# STM32F100_Base_Wireless.net
KiCad netlist of a schematic drawn in EAGLE
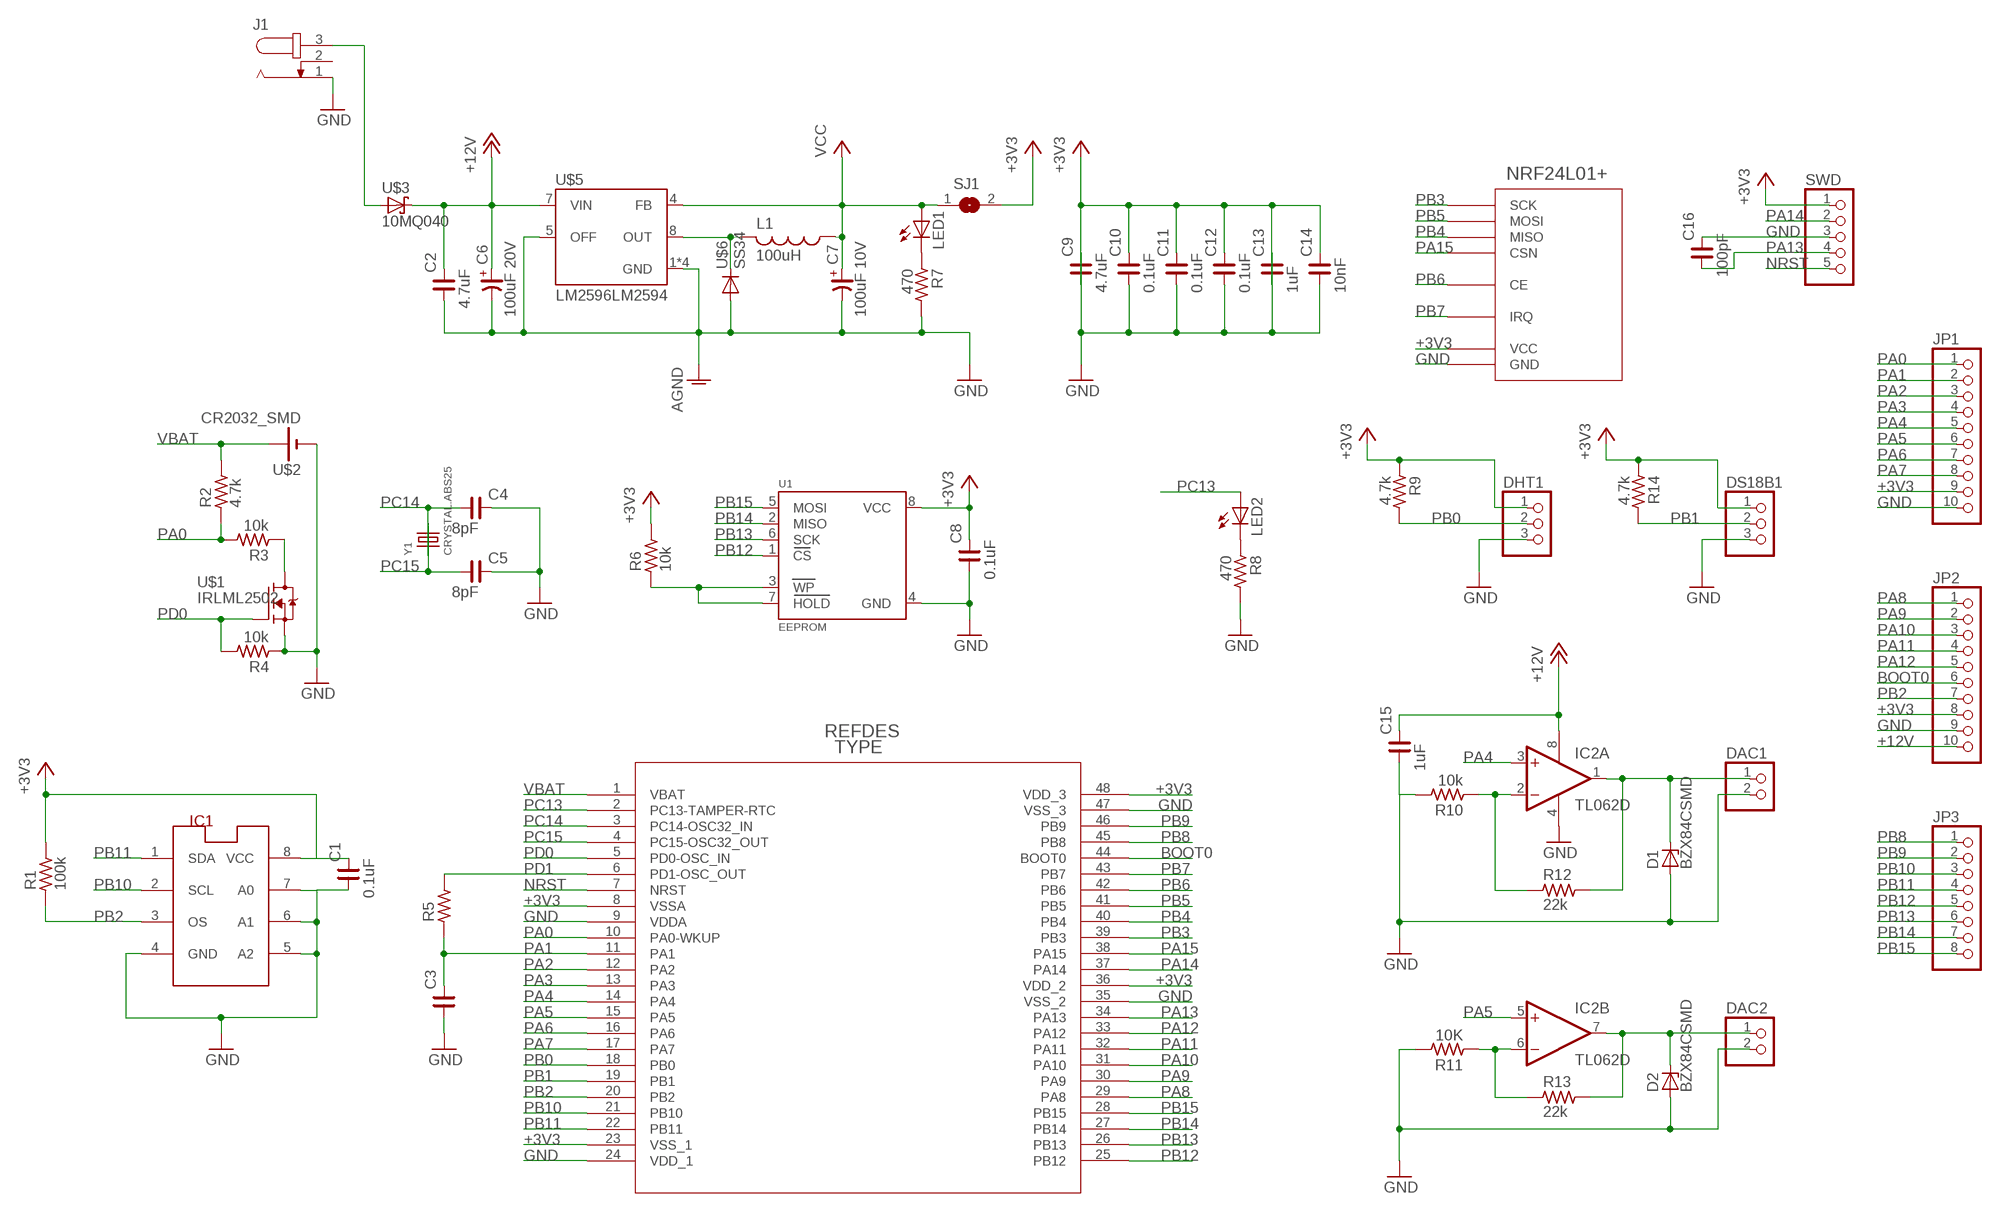
[diagram p0: schematic, sheet 1]

(export (version "E")
  (design (tool "Eeschema 10.0.6"))
  (components
    (comp (ref "C1")
      (value "0.1uF")
      (footprint "eagle-import:C1206")
      (libsource (lib "eagle-import") (part "C_1206"))
    )
    (comp (ref "C2")
      (value "4.7uF")
      (footprint "eagle-import:C1206")
      (libsource (lib "eagle-import") (part "C_1206"))
    )
    (comp (ref "C3")
      (value "C_1206")
      (footprint "eagle-import:C1206")
      (libsource (lib "eagle-import") (part "C_1206"))
    )
    (comp (ref "C4")
      (value "8pF")
      (footprint "eagle-import:C0603")
      (libsource (lib "eagle-import") (part "C_0603"))
    )
    (comp (ref "C5")
      (value "8pF")
      (footprint "eagle-import:C0603")
      (libsource (lib "eagle-import") (part "C_0603"))
    )
    (comp (ref "C6")
      (value "100uF 20V")
      (footprint "eagle-import:C7343_T")
      (libsource (lib "eagle-import") (part "CP_7343"))
    )
    (comp (ref "C7")
      (value "100uF 10V")
      (footprint "eagle-import:C6032-28_T")
      (libsource (lib "eagle-import") (part "CP_6032-28"))
    )
    (comp (ref "C8")
      (value "0.1uF")
      (footprint "eagle-import:C1206")
      (libsource (lib "eagle-import") (part "C_1206"))
    )
    (comp (ref "C9")
      (value "4.7uF")
      (footprint "eagle-import:C1206")
      (libsource (lib "eagle-import") (part "C_1206"))
    )
    (comp (ref "C10")
      (value "0.1uF")
      (footprint "eagle-import:C0603")
      (libsource (lib "eagle-import") (part "C_0603"))
    )
    (comp (ref "C11")
      (value "0.1uF")
      (footprint "eagle-import:C0603")
      (libsource (lib "eagle-import") (part "C_0603"))
    )
    (comp (ref "C12")
      (value "0.1uF")
      (footprint "eagle-import:C0603")
      (libsource (lib "eagle-import") (part "C_0603"))
    )
    (comp (ref "C13")
      (value "1uF")
      (footprint "eagle-import:C1206")
      (libsource (lib "eagle-import") (part "C_1206"))
    )
    (comp (ref "C14")
      (value "10nF")
      (footprint "eagle-import:C0603")
      (libsource (lib "eagle-import") (part "C_0603"))
    )
    (comp (ref "C15")
      (value "1uF")
      (footprint "eagle-import:C1206")
      (libsource (lib "eagle-import") (part "C_1206"))
    )
    (comp (ref "C16")
      (value "100pF")
      (footprint "eagle-import:C1206")
      (libsource (lib "eagle-import") (part "C_1206"))
    )
    (comp (ref "D1")
      (value "BZX84CSMD")
      (footprint "eagle-import:TO236")
      (libsource (lib "eagle-import") (part "BZX84CSMD"))
    )
    (comp (ref "D2")
      (value "BZX84CSMD")
      (footprint "eagle-import:TO236")
      (libsource (lib "eagle-import") (part "BZX84CSMD"))
    )
    (comp (ref "DAC1")
      (value "PINHD-1X02_2.54-S")
      (footprint "eagle-import:1X02-S")
      (libsource (lib "eagle-import") (part "PINHD-1X02_2.54-S"))
    )
    (comp (ref "DAC2")
      (value "PINHD-1X02_2.54-S")
      (footprint "eagle-import:1X02-S")
      (libsource (lib "eagle-import") (part "PINHD-1X02_2.54-S"))
    )
    (comp (ref "DHT1")
      (value "PINHD-1X03_2.54-S")
      (footprint "eagle-import:1X03-S")
      (libsource (lib "eagle-import") (part "PINHD-1X03_2.54-S"))
    )
    (comp (ref "DS18B1")
      (value "PINHD-1X03_2.54-S")
      (footprint "eagle-import:1X03-S")
      (libsource (lib "eagle-import") (part "PINHD-1X03_2.54-S"))
    )
    (comp (ref "IC1")
      (value "LM75_ICN")
      (footprint "eagle-import:SO8_LM75")
      (libsource (lib "eagle-import") (part "LM75_ICN"))
    )
    (comp (ref "IC2")
      (value "TL062D")
      (footprint "eagle-import:SO08")
      (libsource (lib "eagle-import") (part "TL062D"))
    )
    (comp (ref "J1")
      (value "JACK-PLUG0")
      (footprint "eagle-import:SPC4077")
      (libsource (lib "eagle-import") (part "JACK-PLUG0"))
    )
    (comp (ref "JP1")
      (value "PINHD-1X10_2.54-S")
      (footprint "eagle-import:1X10-S")
      (libsource (lib "eagle-import") (part "PINHD-1X10_2.54-S"))
    )
    (comp (ref "JP2")
      (value "PINHD-1X10_2.54-S")
      (footprint "eagle-import:1X10-S")
      (libsource (lib "eagle-import") (part "PINHD-1X10_2.54-S"))
    )
    (comp (ref "JP3")
      (value "PINHD-1X08_2.54-S")
      (footprint "eagle-import:1X08-S")
      (libsource (lib "eagle-import") (part "PINHD-1X08_2.54-S"))
    )
    (comp (ref "L1")
      (value "100uH")
      (footprint "eagle-import:POWER-CHOKE_WE-TPC")
      (libsource (lib "eagle-import") (part "L-USWE-TPC"))
    )
    (comp (ref "LED1")
      (value "LEDCHIPLED_1206")
      (footprint "eagle-import:CHIPLED_1206")
      (libsource (lib "eagle-import") (part "LEDCHIPLED_1206"))
    )
    (comp (ref "LED2")
      (value "LEDCHIPLED_1206")
      (footprint "eagle-import:CHIPLED_1206")
      (libsource (lib "eagle-import") (part "LEDCHIPLED_1206"))
    )
    (comp (ref "R1")
      (value "100k")
      (footprint "eagle-import:R1206")
      (libsource (lib "eagle-import") (part "R_1206"))
    )
    (comp (ref "R2")
      (value "4.7k")
      (footprint "eagle-import:R1206")
      (libsource (lib "eagle-import") (part "R_1206"))
    )
    (comp (ref "R3")
      (value "10k")
      (footprint "eagle-import:R1206")
      (libsource (lib "eagle-import") (part "R_1206"))
    )
    (comp (ref "R4")
      (value "10k")
      (footprint "eagle-import:R1206")
      (libsource (lib "eagle-import") (part "R_1206"))
    )
    (comp (ref "R5")
      (value "R_1206")
      (footprint "eagle-import:R1206")
      (libsource (lib "eagle-import") (part "R_1206"))
    )
    (comp (ref "R6")
      (value "10k")
      (footprint "eagle-import:R1206")
      (libsource (lib "eagle-import") (part "R_1206"))
    )
    (comp (ref "R7")
      (value "470")
      (footprint "eagle-import:R1206")
      (libsource (lib "eagle-import") (part "R_1206"))
    )
    (comp (ref "R8")
      (value "470")
      (footprint "eagle-import:R1206")
      (libsource (lib "eagle-import") (part "R_1206"))
    )
    (comp (ref "R9")
      (value "4.7k")
      (footprint "eagle-import:R1206")
      (libsource (lib "eagle-import") (part "R_1206"))
    )
    (comp (ref "R10")
      (value "10k")
      (footprint "eagle-import:R1206")
      (libsource (lib "eagle-import") (part "R_1206"))
    )
    (comp (ref "R11")
      (value "10K")
      (footprint "eagle-import:R1206")
      (libsource (lib "eagle-import") (part "R_1206"))
    )
    (comp (ref "R12")
      (value "22k")
      (footprint "eagle-import:R1206")
      (libsource (lib "eagle-import") (part "R_1206"))
    )
    (comp (ref "R13")
      (value "22k")
      (footprint "eagle-import:R1206")
      (libsource (lib "eagle-import") (part "R_1206"))
    )
    (comp (ref "R14")
      (value "4.7k")
      (footprint "eagle-import:R1206")
      (libsource (lib "eagle-import") (part "R_1206"))
    )
    (comp (ref "SJ1") (value "SJ") (footprint "eagle-import:SJ") (libsource (lib "eagle-import") (part "SJ")))
    (comp (ref "SWD")
      (value "PINHD-1X05_2.54-90°-S")
      (footprint "eagle-import:1X05_90-S")
      (libsource (lib "eagle-import") (part "PINHD-1X05_2.54-90°-S"))
    )
    (comp (ref "U$1")
      (value "IRLML2502")
      (footprint "eagle-import:SOT23")
      (libsource (lib "eagle-import") (part "IRLML2502"))
    )
    (comp (ref "U$2")
      (value "CR2032_SMD")
      (footprint "eagle-import:SMD_BH-2")
      (libsource (lib "eagle-import") (part "CR2032_SMD"))
    )
    (comp (ref "U$3")
      (value "10MQ040")
      (footprint "eagle-import:SMA")
      (libsource (lib "eagle-import") (part "10MQ040"))
    )
    (comp (ref "U$4")
      (value "STM32F100C8T6B")
      (footprint "eagle-import:LQFP-48")
      (libsource (lib "eagle-import") (part "STM32F100C8T6B"))
    )
    (comp (ref "U$5")
      (value "LM2596LM2594")
      (footprint "eagle-import:SOIC8_150MIL")
      (libsource (lib "eagle-import") (part "LM2596LM2594"))
    )
    (comp (ref "U$6")
      (value "SS34")
      (footprint "eagle-import:DO214AC")
      (libsource (lib "eagle-import") (part "DIODE-DO214AC"))
    )
    (comp (ref "U$7")
      (value "NRF24L01+")
      (footprint "eagle-import:NRF24L01+")
      (libsource (lib "eagle-import") (part "NRF24L01+"))
    )
    (comp (ref "U1")
      (value "EEPROM")
      (footprint "eagle-import:SOIC8_150MIL")
      (libsource (lib "eagle-import") (part "EEPROM_SPI_AT25040A"))
    )
    (comp (ref "Y1")
      (value "CRYSTAL.ABS25")
      (footprint "eagle-import:ABS25")
      (libsource (lib "eagle-import") (part "CRYSTAL.ABS25"))
    )
  )
  (nets
    (net (code "1") (name "+3V3") (class "Default")
      (node (ref "C1") (pin "2") (pinfunction "2_2") (pintype "passive"))
      (node (ref "C10") (pin "2") (pinfunction "2_2") (pintype "passive"))
      (node (ref "C11") (pin "2") (pinfunction "2_2") (pintype "passive"))
      (node (ref "C12") (pin "2") (pinfunction "2_2") (pintype "passive"))
      (node (ref "C13") (pin "1") (pinfunction "1_1") (pintype "passive"))
      (node (ref "C14") (pin "2") (pinfunction "2_2") (pintype "passive"))
      (node (ref "C8") (pin "2") (pinfunction "2_2") (pintype "passive"))
      (node (ref "C9") (pin "1") (pinfunction "1_1") (pintype "passive"))
      (node (ref "DHT1") (pin "1") (pinfunction "1_1") (pintype "passive"))
      (node (ref "DS18B1") (pin "1") (pinfunction "1_1") (pintype "passive"))
      (node (ref "IC1") (pin "8") (pinfunction "VCC_8") (pintype "power_in"))
      (node (ref "JP1") (pin "9") (pinfunction "9_9") (pintype "passive"))
      (node (ref "JP2") (pin "8") (pinfunction "8_8") (pintype "passive"))
      (node (ref "R1") (pin "2") (pinfunction "2_2") (pintype "passive"))
      (node (ref "R14") (pin "1") (pinfunction "1_1") (pintype "passive"))
      (node (ref "R6") (pin "2") (pinfunction "2_2") (pintype "passive"))
      (node (ref "R9") (pin "1") (pinfunction "1_1") (pintype "passive"))
      (node (ref "SJ1") (pin "2") (pinfunction "2_2") (pintype "passive"))
      (node (ref "SWD") (pin "1") (pinfunction "1_1") (pintype "passive"))
      (node (ref "U$4") (pin "23") (pinfunction "VSS_1_23") (pintype "passive"))
      (node (ref "U$4") (pin "36") (pinfunction "VDD_2_36") (pintype "passive"))
      (node (ref "U$4") (pin "48") (pinfunction "VDD_3_48") (pintype "passive"))
      (node (ref "U$4") (pin "8") (pinfunction "VSSA_8") (pintype "passive"))
      (node (ref "U$7") (pin "VCC") (pinfunction "VCC_VCC") (pintype "passive"))
      (node (ref "U1") (pin "8") (pinfunction "VCC_8") (pintype "power_in"))
    )
    (net (code "2") (name "+12V") (class "Default")
      (node (ref "C15") (pin "2") (pinfunction "2_2") (pintype "passive"))
      (node (ref "C2") (pin "2") (pinfunction "2_2") (pintype "passive"))
      (node (ref "C6") (pin "+") (pinfunction "+_+") (pintype "passive"))
      (node (ref "IC2") (pin "8") (pinfunction "V+_8") (pintype "power_in"))
      (node (ref "JP2") (pin "10") (pinfunction "10_10") (pintype "passive"))
      (node (ref "U$3") (pin "C") (pinfunction "C_C") (pintype "passive"))
      (node (ref "U$5") (pin "7") (pinfunction "VIN_7") (pintype "power_in"))
    )
    (net (code "3") (name "/BOOT0") (class "Default")
      (node (ref "JP2") (pin "6") (pinfunction "6_6") (pintype "passive"))
      (node (ref "U$4") (pin "44") (pinfunction "BOOT0_44") (pintype "passive"))
    )
    (net (code "4") (name "/NRST") (class "Default")
      (node (ref "SWD") (pin "5") (pinfunction "5_5") (pintype "passive"))
      (node (ref "U$4") (pin "7") (pinfunction "NRST_7") (pintype "passive"))
    )
    (net (code "5") (name "/PA0") (class "Default")
      (node (ref "JP1") (pin "1") (pinfunction "1_1") (pintype "passive"))
      (node (ref "R2") (pin "1") (pinfunction "1_1") (pintype "passive"))
      (node (ref "R3") (pin "2") (pinfunction "2_2") (pintype "passive"))
      (node (ref "U$4") (pin "10") (pinfunction "PA0-WKUP_10") (pintype "passive"))
    )
    (net (code "6") (name "/PA1") (class "Default")
      (node (ref "C3") (pin "2") (pinfunction "2_2") (pintype "passive"))
      (node (ref "JP1") (pin "2") (pinfunction "2_2") (pintype "passive"))
      (node (ref "R5") (pin "1") (pinfunction "1_1") (pintype "passive"))
      (node (ref "U$4") (pin "11") (pinfunction "PA1_11") (pintype "passive"))
    )
    (net (code "7") (name "/PA2") (class "Default")
      (node (ref "JP1") (pin "3") (pinfunction "3_3") (pintype "passive"))
      (node (ref "U$4") (pin "12") (pinfunction "PA2_12") (pintype "passive"))
    )
    (net (code "8") (name "/PA3") (class "Default")
      (node (ref "JP1") (pin "4") (pinfunction "4_4") (pintype "passive"))
      (node (ref "U$4") (pin "13") (pinfunction "PA3_13") (pintype "passive"))
    )
    (net (code "9") (name "/PA4") (class "Default")
      (node (ref "IC2") (pin "3") (pinfunction "+IN_3") (pintype "input"))
      (node (ref "JP1") (pin "5") (pinfunction "5_5") (pintype "passive"))
      (node (ref "U$4") (pin "14") (pinfunction "PA4_14") (pintype "passive"))
    )
    (net (code "10") (name "/PA5") (class "Default")
      (node (ref "IC2") (pin "5") (pinfunction "+IN_5") (pintype "input"))
      (node (ref "JP1") (pin "6") (pinfunction "6_6") (pintype "passive"))
      (node (ref "U$4") (pin "15") (pinfunction "PA5_15") (pintype "passive"))
    )
    (net (code "11") (name "/PA6") (class "Default")
      (node (ref "JP1") (pin "7") (pinfunction "7_7") (pintype "passive"))
      (node (ref "U$4") (pin "16") (pinfunction "PA6_16") (pintype "passive"))
    )
    (net (code "12") (name "/PA7") (class "Default")
      (node (ref "JP1") (pin "8") (pinfunction "8_8") (pintype "passive"))
      (node (ref "U$4") (pin "17") (pinfunction "PA7_17") (pintype "passive"))
    )
    (net (code "13") (name "/PA8") (class "Default")
      (node (ref "JP2") (pin "1") (pinfunction "1_1") (pintype "passive"))
      (node (ref "U$4") (pin "29") (pinfunction "PA8_29") (pintype "passive"))
    )
    (net (code "14") (name "/PA9") (class "Default")
      (node (ref "JP2") (pin "2") (pinfunction "2_2") (pintype "passive"))
      (node (ref "U$4") (pin "30") (pinfunction "PA9_30") (pintype "passive"))
    )
    (net (code "15") (name "/PA10") (class "Default")
      (node (ref "JP2") (pin "3") (pinfunction "3_3") (pintype "passive"))
      (node (ref "U$4") (pin "31") (pinfunction "PA10_31") (pintype "passive"))
    )
    (net (code "16") (name "/PA11") (class "Default")
      (node (ref "JP2") (pin "4") (pinfunction "4_4") (pintype "passive"))
      (node (ref "U$4") (pin "32") (pinfunction "PA11_32") (pintype "passive"))
    )
    (net (code "17") (name "/PA12") (class "Default")
      (node (ref "JP2") (pin "5") (pinfunction "5_5") (pintype "passive"))
      (node (ref "U$4") (pin "33") (pinfunction "PA12_33") (pintype "passive"))
    )
    (net (code "18") (name "/PA13") (class "Default")
      (node (ref "C16") (pin "1") (pinfunction "1_1") (pintype "passive"))
      (node (ref "SWD") (pin "4") (pinfunction "4_4") (pintype "passive"))
      (node (ref "U$4") (pin "34") (pinfunction "PA13_34") (pintype "passive"))
    )
    (net (code "19") (name "/PA14") (class "Default")
      (node (ref "SWD") (pin "2") (pinfunction "2_2") (pintype "passive"))
      (node (ref "U$4") (pin "37") (pinfunction "PA14_37") (pintype "passive"))
    )
    (net (code "20") (name "/PA15") (class "Default")
      (node (ref "U$4") (pin "38") (pinfunction "PA15_38") (pintype "passive"))
      (node (ref "U$7") (pin "CSN") (pinfunction "CSN_CSN") (pintype "passive"))
    )
    (net (code "21") (name "/PB0") (class "Default")
      (node (ref "DHT1") (pin "2") (pinfunction "2_2") (pintype "passive"))
      (node (ref "R9") (pin "2") (pinfunction "2_2") (pintype "passive"))
      (node (ref "U$4") (pin "18") (pinfunction "PB0_18") (pintype "passive"))
    )
    (net (code "22") (name "/PB1") (class "Default")
      (node (ref "DS18B1") (pin "2") (pinfunction "2_2") (pintype "passive"))
      (node (ref "R14") (pin "2") (pinfunction "2_2") (pintype "passive"))
      (node (ref "U$4") (pin "19") (pinfunction "PB1_19") (pintype "passive"))
    )
    (net (code "23") (name "/PB2") (class "Default")
      (node (ref "IC1") (pin "3") (pinfunction "OS_3") (pintype "output"))
      (node (ref "JP2") (pin "7") (pinfunction "7_7") (pintype "passive"))
      (node (ref "R1") (pin "1") (pinfunction "1_1") (pintype "passive"))
      (node (ref "U$4") (pin "20") (pinfunction "PB2_20") (pintype "passive"))
    )
    (net (code "24") (name "/PB3") (class "Default")
      (node (ref "U$4") (pin "39") (pinfunction "PB3_39") (pintype "passive"))
      (node (ref "U$7") (pin "SCK") (pinfunction "SCK_SCK") (pintype "passive"))
    )
    (net (code "25") (name "/PB4") (class "Default")
      (node (ref "U$4") (pin "40") (pinfunction "PB4_40") (pintype "passive"))
      (node (ref "U$7") (pin "MISO") (pinfunction "MISO_MISO") (pintype "passive"))
    )
    (net (code "26") (name "/PB5") (class "Default")
      (node (ref "U$4") (pin "41") (pinfunction "PB5_41") (pintype "passive"))
      (node (ref "U$7") (pin "MOSI") (pinfunction "MOSI_MOSI") (pintype "passive"))
    )
    (net (code "27") (name "/PB6") (class "Default")
      (node (ref "U$4") (pin "42") (pinfunction "PB6_42") (pintype "passive"))
      (node (ref "U$7") (pin "CE") (pinfunction "CE_CE") (pintype "passive"))
    )
    (net (code "28") (name "/PB7") (class "Default")
      (node (ref "U$4") (pin "43") (pinfunction "PB7_43") (pintype "passive"))
      (node (ref "U$7") (pin "IRQ") (pinfunction "IRQ_IRQ") (pintype "passive"))
    )
    (net (code "29") (name "/PB8") (class "Default")
      (node (ref "JP3") (pin "1") (pinfunction "1_1") (pintype "passive"))
      (node (ref "U$4") (pin "45") (pinfunction "PB8_45") (pintype "passive"))
    )
    (net (code "30") (name "/PB9") (class "Default")
      (node (ref "JP3") (pin "2") (pinfunction "2_2") (pintype "passive"))
      (node (ref "U$4") (pin "46") (pinfunction "PB9_46") (pintype "passive"))
    )
    (net (code "31") (name "/PB10") (class "Default")
      (node (ref "IC1") (pin "2") (pinfunction "SCL_2") (pintype "bidirectional"))
      (node (ref "JP3") (pin "3") (pinfunction "3_3") (pintype "passive"))
      (node (ref "U$4") (pin "21") (pinfunction "PB10_21") (pintype "passive"))
    )
    (net (code "32") (name "/PB11") (class "Default")
      (node (ref "IC1") (pin "1") (pinfunction "SDA_1") (pintype "bidirectional"))
      (node (ref "JP3") (pin "4") (pinfunction "4_4") (pintype "passive"))
      (node (ref "U$4") (pin "22") (pinfunction "PB11_22") (pintype "passive"))
    )
    (net (code "33") (name "/PB12") (class "Default")
      (node (ref "JP3") (pin "5") (pinfunction "5_5") (pintype "passive"))
      (node (ref "U$4") (pin "25") (pinfunction "PB12_25") (pintype "passive"))
      (node (ref "U1") (pin "1") (pinfunction "CS_1") (pintype "bidirectional"))
    )
    (net (code "34") (name "/PB13") (class "Default")
      (node (ref "JP3") (pin "6") (pinfunction "6_6") (pintype "passive"))
      (node (ref "U$4") (pin "26") (pinfunction "PB13_26") (pintype "passive"))
      (node (ref "U1") (pin "6") (pinfunction "SCK_6") (pintype "bidirectional"))
    )
    (net (code "35") (name "/PB14") (class "Default")
      (node (ref "JP3") (pin "7") (pinfunction "7_7") (pintype "passive"))
      (node (ref "U$4") (pin "27") (pinfunction "PB14_27") (pintype "passive"))
      (node (ref "U1") (pin "2") (pinfunction "MISO_2") (pintype "bidirectional"))
    )
    (net (code "36") (name "/PB15") (class "Default")
      (node (ref "JP3") (pin "8") (pinfunction "8_8") (pintype "passive"))
      (node (ref "U$4") (pin "28") (pinfunction "PB15_28") (pintype "passive"))
      (node (ref "U1") (pin "5") (pinfunction "MOSI_5") (pintype "bidirectional"))
    )
    (net (code "37") (name "/PC13") (class "Default")
      (node (ref "LED2") (pin "A") (pinfunction "A_A") (pintype "passive"))
      (node (ref "U$4") (pin "2") (pinfunction "PC13-TAMPER-RTC_2") (pintype "passive"))
    )
    (net (code "38") (name "/PC14") (class "Default")
      (node (ref "C4") (pin "1") (pinfunction "1_1") (pintype "passive"))
      (node (ref "U$4") (pin "3") (pinfunction "PC14-OSC32_IN_3") (pintype "passive"))
      (node (ref "Y1") (pin "1") (pinfunction "1_1") (pintype "passive"))
    )
    (net (code "39") (name "/PC15") (class "Default")
      (node (ref "C5") (pin "1") (pinfunction "1_1") (pintype "passive"))
      (node (ref "U$4") (pin "4") (pinfunction "PC15-OSC32_OUT_4") (pintype "passive"))
      (node (ref "Y1") (pin "4") (pinfunction "2_4") (pintype "passive"))
    )
    (net (code "40") (name "/PD0") (class "Default")
      (node (ref "R4") (pin "2") (pinfunction "2_2") (pintype "passive"))
      (node (ref "U$1") (pin "1") (pinfunction "G_1") (pintype "passive"))
      (node (ref "U$4") (pin "5") (pinfunction "PD0-OSC_IN_5") (pintype "passive"))
    )
    (net (code "41") (name "/PD1") (class "Default")
      (node (ref "R5") (pin "2") (pinfunction "2_2") (pintype "passive"))
      (node (ref "U$4") (pin "6") (pinfunction "PD1-OSC_OUT_6") (pintype "passive"))
    )
    (net (code "42") (name "/VBAT") (class "Default")
      (node (ref "R2") (pin "2") (pinfunction "2_2") (pintype "passive"))
      (node (ref "U$2") (pin "P$POS1") (pinfunction "+_P$POS1") (pintype "passive"))
      (node (ref "U$4") (pin "1") (pinfunction "VBAT_1") (pintype "passive"))
    )
    (net (code "43") (name "AGND") (class "Default")
      (node (ref "C1") (pin "1") (pinfunction "1_1") (pintype "passive"))
      (node (ref "C10") (pin "1") (pinfunction "1_1") (pintype "passive"))
      (node (ref "C11") (pin "1") (pinfunction "1_1") (pintype "passive"))
      (node (ref "C12") (pin "1") (pinfunction "1_1") (pintype "passive"))
      (node (ref "C13") (pin "2") (pinfunction "2_2") (pintype "passive"))
      (node (ref "C14") (pin "1") (pinfunction "1_1") (pintype "passive"))
      (node (ref "C15") (pin "1") (pinfunction "1_1") (pintype "passive"))
      (node (ref "C16") (pin "2") (pinfunction "2_2") (pintype "passive"))
      (node (ref "C2") (pin "1") (pinfunction "1_1") (pintype "passive"))
      (node (ref "C3") (pin "1") (pinfunction "1_1") (pintype "passive"))
      (node (ref "C4") (pin "2") (pinfunction "2_2") (pintype "passive"))
      (node (ref "C5") (pin "2") (pinfunction "2_2") (pintype "passive"))
      (node (ref "C6") (pin "-") (pinfunction "-_-") (pintype "passive"))
      (node (ref "C7") (pin "-") (pinfunction "-_-") (pintype "passive"))
      (node (ref "C8") (pin "1") (pinfunction "1_1") (pintype "passive"))
      (node (ref "C9") (pin "2") (pinfunction "2_2") (pintype "passive"))
      (node (ref "D1") (pin "A") (pinfunction "A_A") (pintype "passive"))
      (node (ref "D2") (pin "A") (pinfunction "A_A") (pintype "passive"))
      (node (ref "DAC1") (pin "2") (pinfunction "2_2") (pintype "passive"))
      (node (ref "DAC2") (pin "2") (pinfunction "2_2") (pintype "passive"))
      (node (ref "DHT1") (pin "3") (pinfunction "3_3") (pintype "passive"))
      (node (ref "DS18B1") (pin "3") (pinfunction "3_3") (pintype "passive"))
      (node (ref "IC1") (pin "4") (pinfunction "GND_4") (pintype "power_in"))
      (node (ref "IC1") (pin "5") (pinfunction "A2_5") (pintype "input"))
      (node (ref "IC1") (pin "6") (pinfunction "A1_6") (pintype "input"))
      (node (ref "IC1") (pin "7") (pinfunction "A0_7") (pintype "input"))
      (node (ref "IC2") (pin "4") (pinfunction "V-_4") (pintype "power_in"))
      (node (ref "J1") (pin "1") (pinfunction "1_1") (pintype "passive"))
      (node (ref "JP1") (pin "10") (pinfunction "10_10") (pintype "passive"))
      (node (ref "JP2") (pin "9") (pinfunction "9_9") (pintype "passive"))
      (node (ref "R10") (pin "2") (pinfunction "2_2") (pintype "passive"))
      (node (ref "R11") (pin "2") (pinfunction "2_2") (pintype "passive"))
      (node (ref "R4") (pin "1") (pinfunction "1_1") (pintype "passive"))
      (node (ref "R7") (pin "2") (pinfunction "2_2") (pintype "passive"))
      (node (ref "R8") (pin "2") (pinfunction "2_2") (pintype "passive"))
      (node (ref "SWD") (pin "3") (pinfunction "3_3") (pintype "passive"))
      (node (ref "U$1") (pin "2") (pinfunction "S_2") (pintype "passive"))
      (node (ref "U$2") (pin "P$NEG") (pinfunction "-_P$NEG") (pintype "passive"))
      (node (ref "U$4") (pin "24") (pinfunction "VDD_1_24") (pintype "passive"))
      (node (ref "U$4") (pin "35") (pinfunction "VSS_2_35") (pintype "passive"))
      (node (ref "U$4") (pin "47") (pinfunction "VSS_3_47") (pintype "passive"))
      (node (ref "U$4") (pin "9") (pinfunction "VDDA_9") (pintype "passive"))
      (node (ref "U$5") (pin "1") (pinfunction "GND_1") (pintype "power_in"))
      (node (ref "U$5") (pin "2") (pinfunction "GND_2") (pintype "power_in"))
      (node (ref "U$5") (pin "3") (pinfunction "GND_3") (pintype "power_in"))
      (node (ref "U$5") (pin "5") (pinfunction "OFF_5") (pintype "input"))
      (node (ref "U$5") (pin "6") (pinfunction "GND_6") (pintype "power_in"))
      (node (ref "U$6") (pin "A") (pinfunction "A_A") (pintype "passive"))
      (node (ref "U$7") (pin "GND") (pinfunction "GND_GND") (pintype "passive"))
      (node (ref "U1") (pin "4") (pinfunction "GND_4") (pintype "power_in"))
    )
    (net (code "44") (name "Net-(IC2A--IN)") (class "Default")
      (node (ref "IC2") (pin "2") (pinfunction "-IN_2") (pintype "input"))
      (node (ref "R10") (pin "1") (pinfunction "1_1") (pintype "passive"))
      (node (ref "R12") (pin "1") (pinfunction "1_1") (pintype "passive"))
    )
    (net (code "45") (name "Net-(IC2A-OUT)") (class "Default")
      (node (ref "D1") (pin "C") (pinfunction "C_C") (pintype "passive"))
      (node (ref "DAC1") (pin "1") (pinfunction "1_1") (pintype "passive"))
      (node (ref "IC2") (pin "1") (pinfunction "OUT_1") (pintype "output"))
      (node (ref "R12") (pin "2") (pinfunction "2_2") (pintype "passive"))
    )
    (net (code "46") (name "Net-(IC2B--IN)") (class "Default")
      (node (ref "IC2") (pin "6") (pinfunction "-IN_6") (pintype "input"))
      (node (ref "R11") (pin "1") (pinfunction "1_1") (pintype "passive"))
      (node (ref "R13") (pin "1") (pinfunction "1_1") (pintype "passive"))
    )
    (net (code "47") (name "Net-(IC2B-OUT)") (class "Default")
      (node (ref "D2") (pin "C") (pinfunction "C_C") (pintype "passive"))
      (node (ref "DAC2") (pin "1") (pinfunction "1_1") (pintype "passive"))
      (node (ref "IC2") (pin "7") (pinfunction "OUT_7") (pintype "output"))
      (node (ref "R13") (pin "2") (pinfunction "2_2") (pintype "passive"))
    )
    (net (code "48") (name "Net-(J1-Pad3)") (class "Default")
      (node (ref "J1") (pin "3") (pinfunction "3_3") (pintype "passive"))
      (node (ref "U$3") (pin "A") (pinfunction "A_A") (pintype "passive"))
    )
    (net (code "49") (name "Net-(LED1-PadC)") (class "Default")
      (node (ref "LED1") (pin "C") (pinfunction "C_C") (pintype "passive"))
      (node (ref "R7") (pin "1") (pinfunction "1_1") (pintype "passive"))
    )
    (net (code "50") (name "Net-(LED2-PadC)") (class "Default")
      (node (ref "LED2") (pin "C") (pinfunction "C_C") (pintype "passive"))
      (node (ref "R8") (pin "1") (pinfunction "1_1") (pintype "passive"))
    )
    (net (code "51") (name "Net-(U$1-D)") (class "Default")
      (node (ref "R3") (pin "1") (pinfunction "1_1") (pintype "passive"))
      (node (ref "U$1") (pin "3") (pinfunction "D_3") (pintype "passive"))
    )
    (net (code "52") (name "Net-(U$5-OUT)") (class "Default")
      (node (ref "L1") (pin "2") (pinfunction "2_2") (pintype "passive"))
      (node (ref "U$5") (pin "8") (pinfunction "OUT_8") (pintype "output"))
      (node (ref "U$6") (pin "C") (pinfunction "C_C") (pintype "passive"))
    )
    (net (code "53") (name "Net-(U1-HOLD)") (class "Default")
      (node (ref "R6") (pin "1") (pinfunction "1_1") (pintype "passive"))
      (node (ref "U1") (pin "3") (pinfunction "WP_3") (pintype "bidirectional"))
      (node (ref "U1") (pin "7") (pinfunction "HOLD_7") (pintype "bidirectional"))
    )
    (net (code "54") (name "VCC") (class "Default")
      (node (ref "C7") (pin "+") (pinfunction "+_+") (pintype "passive"))
      (node (ref "L1") (pin "1") (pinfunction "1_1") (pintype "passive"))
      (node (ref "LED1") (pin "A") (pinfunction "A_A") (pintype "passive"))
      (node (ref "SJ1") (pin "1") (pinfunction "1_1") (pintype "passive"))
      (node (ref "U$5") (pin "4") (pinfunction "FB_4") (pintype "input"))
    )
    (net (code "55") (name "unconnected-(J1-Pad2)") (class "Default")
      (node (ref "J1") (pin "2") (pinfunction "2_2") (pintype "passive"))
    )
  )
)
